# input_output.net
KiCad netlist of a schematic drawn in Altium Designer
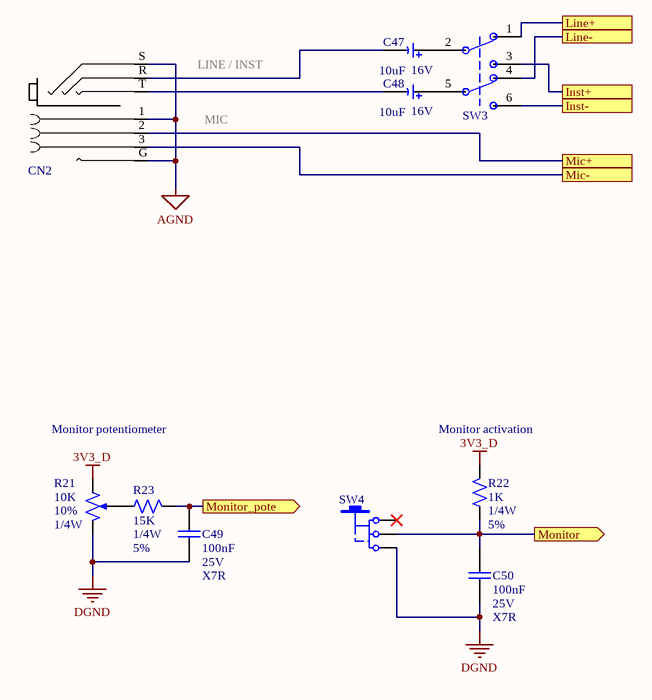
[diagram p0: input_output.SchDoc]

(export (version "E")
  (design (tool "Eeschema 10.0.6"))
  (components
    (comp (ref "C47")
      (value "Capacitor polarizado")
      (footprint "CAP_Electrolytic")
      (fields (field (name "VALOR") "10uF") (field (name "TENSION") "16V"))
      (libsource (lib "sch_comunes") (part "Capacitor polarizado"))
    )
    (comp (ref "C48")
      (value "Capacitor polarizado")
      (footprint "CAP_Electrolytic")
      (fields (field (name "VALOR") "10uF") (field (name "TENSION") "16V"))
      (libsource (lib "sch_comunes") (part "Capacitor polarizado"))
    )
    (comp (ref "C49")
      (value "Capacitor")
      (footprint "C0805")
      (description "Capacitor de placas paralelas")
      (fields (field (name "VALOR") "100nF") (field (name "TENSION") "25V") (field (name "TOLERANCIA") "X7R"))
      (libsource (lib "sch_comunes") (part "Capacitor"))
    )
    (comp (ref "C50")
      (value "Capacitor")
      (footprint "C0805")
      (description "Capacitor de placas paralelas")
      (fields (field (name "VALOR") "100nF") (field (name "TENSION") "25V") (field (name "TOLERANCIA") "X7R"))
      (libsource (lib "sch_comunes") (part "Capacitor"))
    )
    (comp (ref "CN2")
      (value "XRL_Jack_Combo_stereo")
      (footprint "Combo XLR Jack")
      (libsource (lib "Sch_Conectores") (part "XRL_Jack_Combo_stereo"))
    )
    (comp (ref "R21")
      (value "Potenciometro")
      (footprint "Header 3x1")
      (fields (field (name "VALOR") "10K") (field (name "TOLERANCIA") "10%") (field (name "POTENCIA") "1/4W"))
      (libsource (lib "Sch_Comunes") (part "Potenciometer"))
    )
    (comp (ref "R22")
      (value "Resistor")
      (footprint "R0805")
      (description "Resistencia")
      (fields (field (name "VALOR") "1K") (field (name "POTENCIA") "1/4W") (field (name "TOLERANCIA") "5%"))
      (libsource (lib "sch_comunes") (part "Resistor"))
    )
    (comp (ref "R23")
      (value "Resistor")
      (footprint "R0805")
      (description "Resistencia")
      (fields (field (name "VALOR") "15K") (field (name "POTENCIA") "1/4W") (field (name "TOLERANCIA") "5%"))
      (libsource (lib "sch_comunes") (part "Resistor"))
    )
    (comp (ref "SW3")
      (value "Slide_SW_DPDT")
      (footprint "DPDT_SMD_Slide_90º")
      (libsource (lib "sch_comunes") (part "Slide_SW_DPDT"))
    )
    (comp (ref "SW4")
      (value "TAC_SWITCH_4")
      (footprint "SPDT_SMD_90º")
      (description "Pulsador de 4 pines")
      (libsource (lib "sch_comunes") (part "SWITCH_3"))
    )
  )
  (nets
    (net (code "1") (name "/Inst+") (class "Default")
      (node (ref "SW3") (pin "3") (pinfunction "3_3") (pintype "passive"))
    )
    (net (code "2") (name "/Inst-") (class "Default")
      (node (ref "SW3") (pin "6") (pinfunction "6_6") (pintype "passive"))
    )
    (net (code "3") (name "/Line+") (class "Default")
      (node (ref "SW3") (pin "1") (pinfunction "1_1") (pintype "passive"))
    )
    (net (code "4") (name "/Line-") (class "Default")
      (node (ref "SW3") (pin "4") (pinfunction "4_4") (pintype "passive"))
    )
    (net (code "5") (name "/Mic+") (class "Default") (node (ref "CN2") (pin "2") (pintype "passive")))
    (net (code "6") (name "/Mic-") (class "Default") (node (ref "CN2") (pin "3") (pintype "passive")))
    (net (code "7") (name "/Monitor") (class "Default")
      (node (ref "C50") (pin "1") (pinfunction "1_1") (pintype "passive"))
      (node (ref "R22") (pin "1") (pinfunction "1_1") (pintype "passive"))
      (node (ref "SW4") (pin "2") (pinfunction "2_2") (pintype "passive"))
    )
    (net (code "8") (name "/Monitor_pote") (class "Default")
      (node (ref "C49") (pin "1") (pinfunction "1_1") (pintype "passive"))
      (node (ref "R23") (pin "2") (pinfunction "2_2") (pintype "passive"))
    )
    (net (code "9") (name "3V3_D") (class "Default")
      (node (ref "R21") (pin "3") (pinfunction "Right_3") (pintype "passive"))
      (node (ref "R22") (pin "2") (pinfunction "2_2") (pintype "passive"))
    )
    (net (code "10") (name "AGND") (class "Default")
      (node (ref "CN2") (pin "1") (pintype "passive"))
      (node (ref "CN2") (pin "G") (pintype "passive"))
      (node (ref "CN2") (pin "S") (pintype "passive"))
    )
    (net (code "11") (name "DGND") (class "Default")
      (node (ref "C49") (pin "2") (pinfunction "2_2") (pintype "passive"))
      (node (ref "C50") (pin "2") (pinfunction "2_2") (pintype "passive"))
      (node (ref "R21") (pin "1") (pinfunction "Left_1") (pintype "passive"))
      (node (ref "SW4") (pin "3") (pinfunction "3_3") (pintype "passive"))
    )
    (net (code "12") (name "Net-(C47-Pad1)") (class "Default")
      (node (ref "C47") (pin "1") (pinfunction "1_1") (pintype "passive"))
      (node (ref "SW3") (pin "2") (pinfunction "2_2") (pintype "passive"))
    )
    (net (code "13") (name "Net-(C47-Pad2)") (class "Default")
      (node (ref "C47") (pin "2") (pinfunction "2_2") (pintype "passive"))
      (node (ref "CN2") (pin "R") (pintype "passive"))
    )
    (net (code "14") (name "Net-(C48-Pad1)") (class "Default")
      (node (ref "C48") (pin "1") (pinfunction "1_1") (pintype "passive"))
      (node (ref "SW3") (pin "5") (pinfunction "5_5") (pintype "passive"))
    )
    (net (code "15") (name "Net-(C48-Pad2)") (class "Default")
      (node (ref "C48") (pin "2") (pinfunction "2_2") (pintype "passive"))
      (node (ref "CN2") (pin "T") (pintype "passive"))
    )
    (net (code "16") (name "Net-(R21-Punto_medio)") (class "Default")
      (node (ref "R21") (pin "2") (pinfunction "Punto_medio_2") (pintype "passive"))
      (node (ref "R23") (pin "1") (pinfunction "1_1") (pintype "passive"))
    )
    (net (code "17") (name "unconnected-(SW4-Pad1)") (class "Default")
      (node (ref "SW4") (pin "1") (pinfunction "1_1") (pintype "passive+no_connect"))
    )
  )
)
